# Connectors.net
KiCad netlist of a schematic drawn in Altium Designer
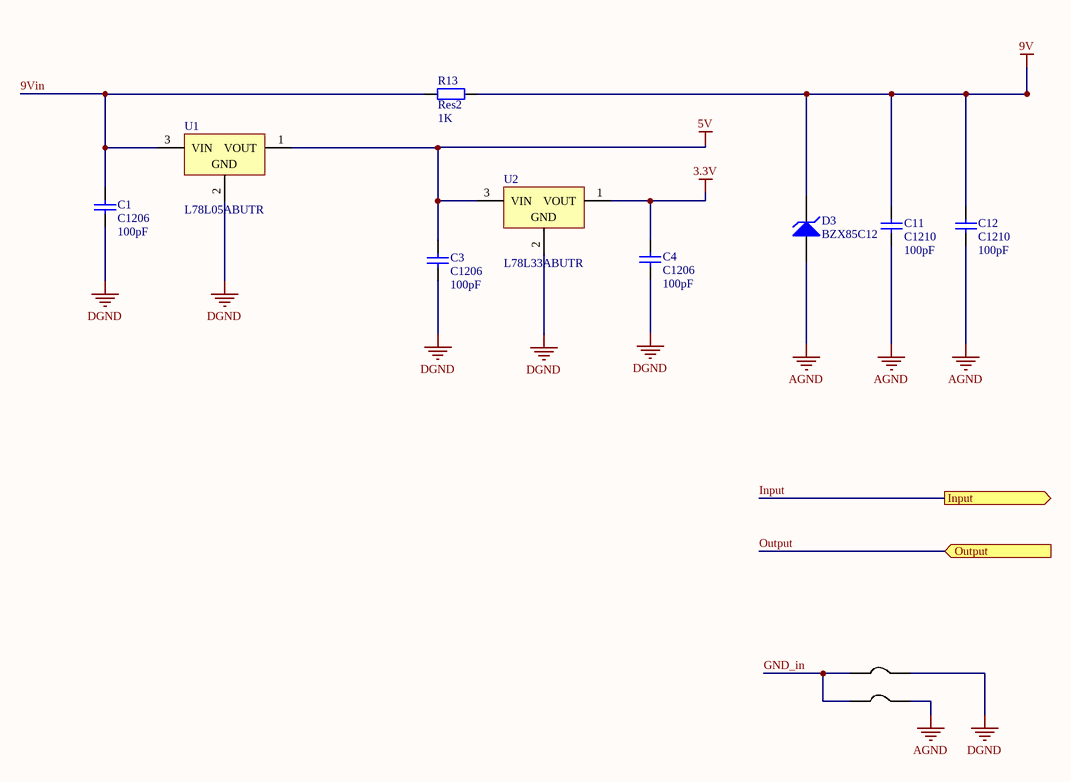
[diagram p0: Connectors.SchDoc]

(export (version "E")
  (design (tool "Eeschema 10.0.6"))
  (components
    (comp (ref "C1")
      (value "C1206")
      (footprint "1206")
      (description "Ceramic Chip Capacitor - Standard")
      (fields (field (name "ALTIUM_VALUE") "100pF") (field (name "PUBLISHER") "Altium Limited"))
      (libsource (lib "KEMET Chip Capacitor") (part "C1206"))
    )
    (comp (ref "C3")
      (value "C1206")
      (footprint "1206")
      (description "Ceramic Chip Capacitor - Standard")
      (fields (field (name "ALTIUM_VALUE") "100pF") (field (name "PUBLISHER") "Altium Limited"))
      (libsource (lib "KEMET Chip Capacitor") (part "C1206"))
    )
    (comp (ref "C4")
      (value "C1206")
      (footprint "1206")
      (description "Ceramic Chip Capacitor - Standard")
      (fields (field (name "ALTIUM_VALUE") "100pF") (field (name "PUBLISHER") "Altium Limited"))
      (libsource (lib "KEMET Chip Capacitor") (part "C1206"))
    )
    (comp (ref "C11")
      (value "C1210")
      (footprint "1210")
      (description "Ceramic Chip Capacitor - Standard")
      (fields (field (name "ALTIUM_VALUE") "100pF") (field (name "PUBLISHER") "Altium Limited"))
      (libsource (lib "KEMET Chip Capacitor") (part "C1210"))
    )
    (comp (ref "C12")
      (value "C1210")
      (footprint "1210")
      (description "Ceramic Chip Capacitor - Standard")
      (fields (field (name "ALTIUM_VALUE") "100pF") (field (name "PUBLISHER") "Altium Limited"))
      (libsource (lib "KEMET Chip Capacitor") (part "C1210"))
    )
    (comp (ref "D3")
      (value "BZX85C12")
      (footprint "DO41")
      (description "Silicon Epitaxial Planar Zener Diode (1W)")
      (fields (field (name "PUBLISHER") "Altium Limited"))
      (libsource (lib "Vishay Telefunken Discrete Diode") (part "BZX85C12"))
    )
    (comp (ref "JMP1") (value "Jumper") (footprint "Jumper") (libsource (lib "Parts") (part "Jumper")))
    (comp (ref "JMP2") (value "Jumper") (footprint "Jumper") (libsource (lib "Parts") (part "Jumper")))
    (comp (ref "R13")
      (value "Res2")
      (footprint "AXIAL-0.4")
      (description "Resistor")
      (fields (field (name "ALTIUM_VALUE") "1K") (field (name "PUBLISHER") "Altium Limited"))
      (libsource (lib "Miscellaneous Devices") (part "Res2"))
    )
    (comp (ref "U1")
      (value "L78L05ABUTR")
      (footprint "SOT-89_N")
      (description "Positive Voltage Regulator, 5V, 4-Pin SOT-89, Tape and Reel")
      (libsource (lib "STMicroelectronics Power Management Linear Regulator") (part "L78L05ABUTR"))
    )
    (comp (ref "U2")
      (value "L78L33ABUTR")
      (footprint "SOT-89_N")
      (description "Positive Voltage Regulator, 3.3V, 4-Pin SOT-89, Tape and Reel")
      (libsource (lib "STMicroelectronics Power Management Linear Regulator") (part "L78L33ABUTR"))
    )
  )
  (nets
    (net (code "1") (name "/9Vin") (class "Default")
      (node (ref "C1") (pin "2") (pinfunction "2_2") (pintype "passive"))
      (node (ref "R13") (pin "1") (pinfunction "1_1") (pintype "passive"))
      (node (ref "U1") (pin "3") (pinfunction "VIN_3") (pintype "power_in"))
    )
    (net (code "2") (name "/GND_in") (class "Default")
      (node (ref "JMP1") (pin "1") (pinfunction "1_1") (pintype "passive"))
      (node (ref "JMP2") (pin "1") (pinfunction "1_1") (pintype "passive"))
    )
    (net (code "5") (name "3.3V") (class "Default")
      (node (ref "C4") (pin "2") (pinfunction "2_2") (pintype "passive"))
      (node (ref "U2") (pin "1") (pinfunction "VOUT_1") (pintype "power_in"))
    )
    (net (code "6") (name "5V") (class "Default")
      (node (ref "C3") (pin "2") (pinfunction "2_2") (pintype "passive"))
      (node (ref "U1") (pin "1") (pinfunction "VOUT_1") (pintype "power_in"))
      (node (ref "U2") (pin "3") (pinfunction "VIN_3") (pintype "power_in"))
    )
    (net (code "7") (name "9V") (class "Default")
      (node (ref "C11") (pin "2") (pinfunction "2_2") (pintype "passive"))
      (node (ref "C12") (pin "2") (pinfunction "2_2") (pintype "passive"))
      (node (ref "D3") (pin "2") (pinfunction "K_2") (pintype "passive"))
      (node (ref "R13") (pin "2") (pinfunction "2_2") (pintype "passive"))
    )
    (net (code "8") (name "AGND") (class "Default")
      (node (ref "C11") (pin "1") (pinfunction "1_1") (pintype "passive"))
      (node (ref "C12") (pin "1") (pinfunction "1_1") (pintype "passive"))
      (node (ref "D3") (pin "1") (pinfunction "A_1") (pintype "passive"))
      (node (ref "JMP2") (pin "2") (pinfunction "2_2") (pintype "passive"))
    )
    (net (code "9") (name "DGND") (class "Default")
      (node (ref "C1") (pin "1") (pinfunction "1_1") (pintype "passive"))
      (node (ref "C3") (pin "1") (pinfunction "1_1") (pintype "passive"))
      (node (ref "C4") (pin "1") (pinfunction "1_1") (pintype "passive"))
      (node (ref "JMP1") (pin "2") (pinfunction "2_2") (pintype "passive"))
      (node (ref "U1") (pin "2") (pinfunction "GND_2") (pintype "power_in"))
      (node (ref "U2") (pin "2") (pinfunction "GND_2") (pintype "power_in"))
    )
  )
)
